# G803X.net
KiCad netlist of a schematic drawn in EAGLE
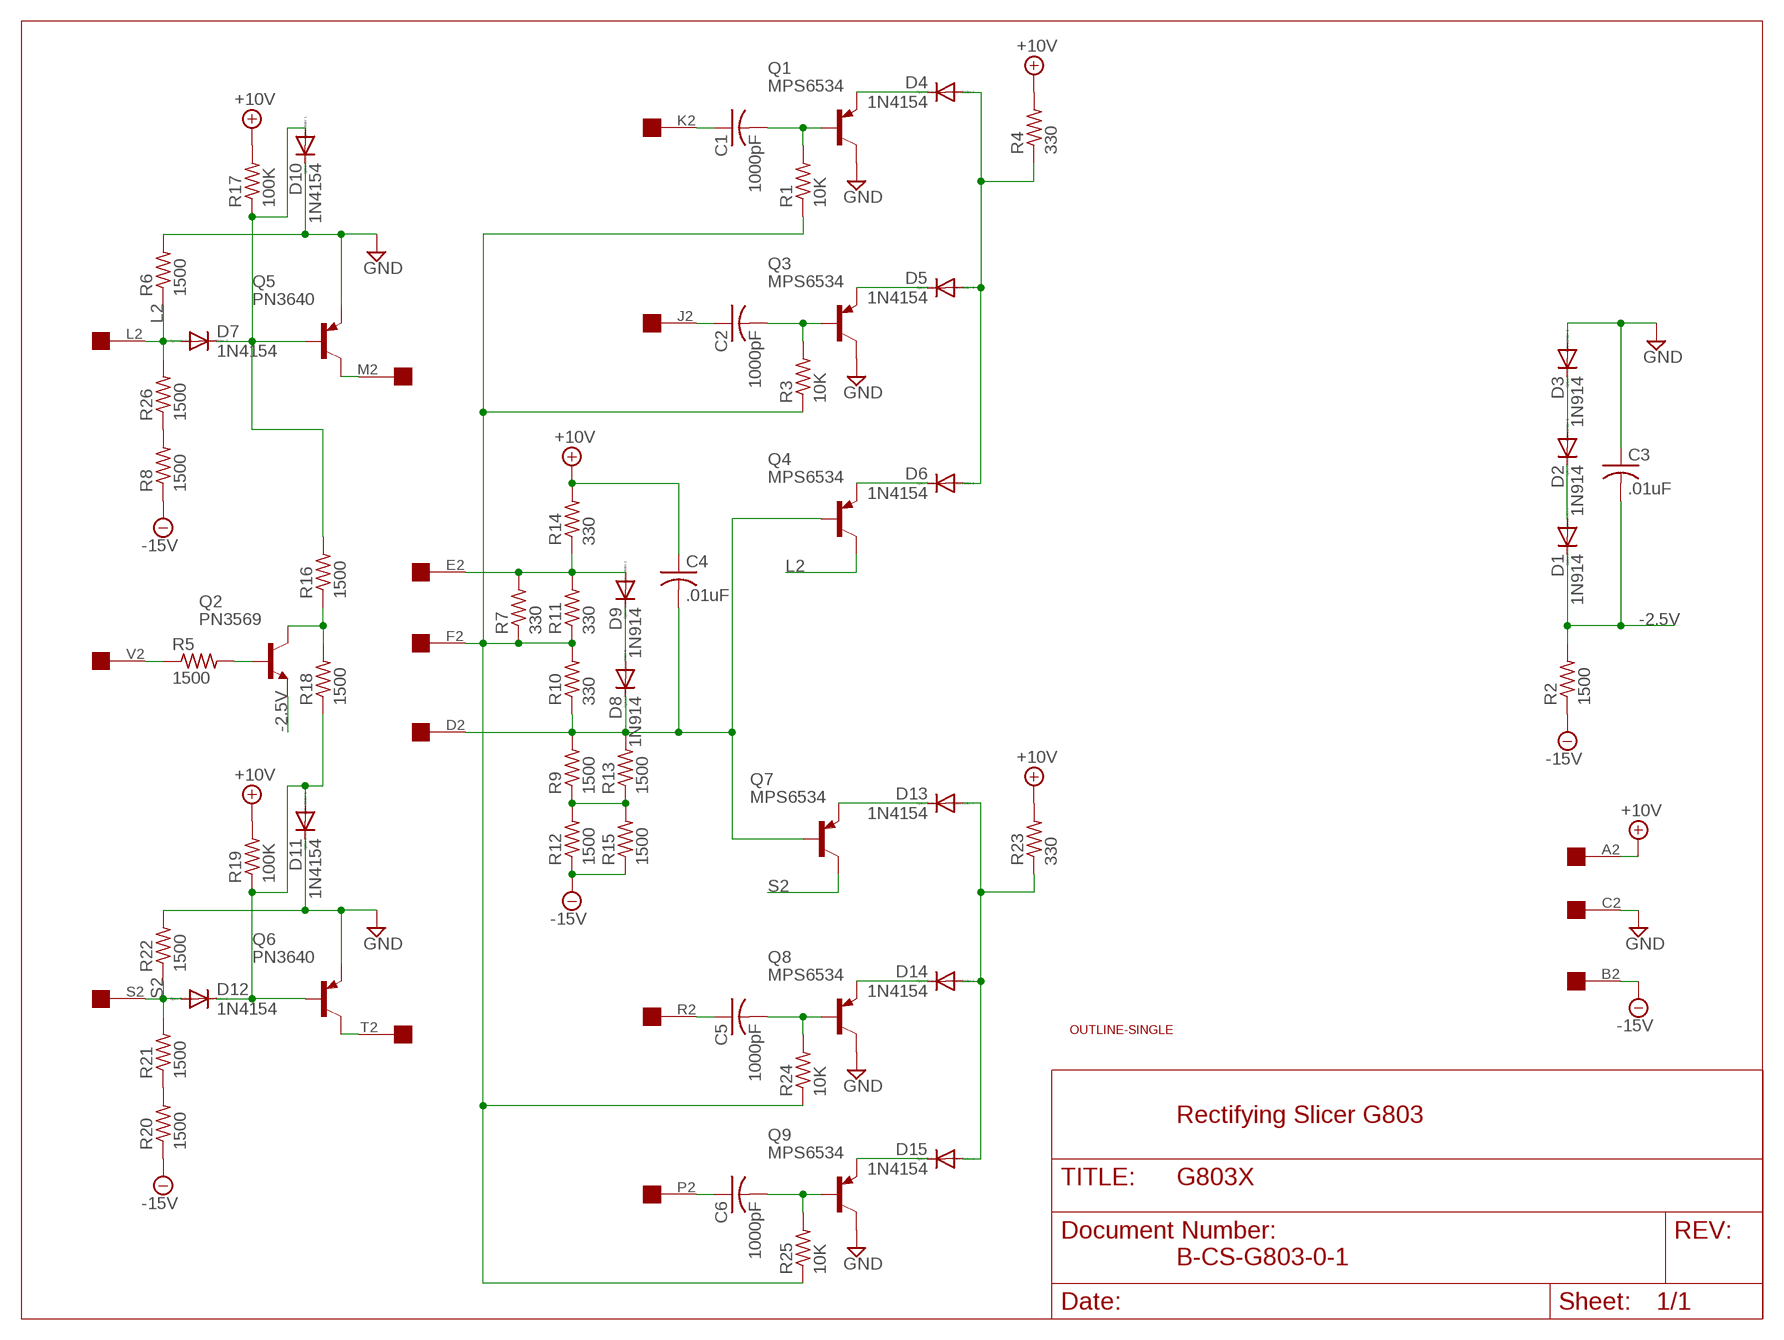
[diagram p0: schematic, sheet 1]

(export (version "E")
  (design (tool "Eeschema 10.0.6"))
  (components
    (comp (ref "C1")
      (value "1000pF")
      (footprint "eagle-import:C075-032X103")
      (libsource (lib "eagle-import") (part "C-US075-032X103"))
    )
    (comp (ref "C2")
      (value "1000pF")
      (footprint "eagle-import:C075-032X103")
      (libsource (lib "eagle-import") (part "C-US075-032X103"))
    )
    (comp (ref "C3")
      (value ".01uF")
      (footprint "eagle-import:C050-025X075")
      (libsource (lib "eagle-import") (part "C-US050-025X075"))
    )
    (comp (ref "C4")
      (value ".01uF")
      (footprint "eagle-import:C075-032X103")
      (libsource (lib "eagle-import") (part "C-US075-032X103"))
    )
    (comp (ref "C5")
      (value "1000pF")
      (footprint "eagle-import:C075-032X103")
      (libsource (lib "eagle-import") (part "C-US075-032X103"))
    )
    (comp (ref "C6")
      (value "1000pF")
      (footprint "eagle-import:C075-032X103")
      (libsource (lib "eagle-import") (part "C-US075-032X103"))
    )
    (comp (ref "D1")
      (value "1N914")
      (footprint "eagle-import:DO35-10")
      (libsource (lib "eagle-import") (part "1N4148DO35-10"))
    )
    (comp (ref "D2")
      (value "1N914")
      (footprint "eagle-import:DO35-10")
      (libsource (lib "eagle-import") (part "1N4148DO35-10"))
    )
    (comp (ref "D3")
      (value "1N914")
      (footprint "eagle-import:DO35-10")
      (libsource (lib "eagle-import") (part "1N4148DO35-10"))
    )
    (comp (ref "D4")
      (value "1N4154")
      (footprint "eagle-import:DO35-10")
      (libsource (lib "eagle-import") (part "1N4148DO35-10"))
    )
    (comp (ref "D5")
      (value "1N4154")
      (footprint "eagle-import:DO35-10")
      (libsource (lib "eagle-import") (part "1N4148DO35-10"))
    )
    (comp (ref "D6")
      (value "1N4154")
      (footprint "eagle-import:DO35-10")
      (libsource (lib "eagle-import") (part "1N4148DO35-10"))
    )
    (comp (ref "D7")
      (value "1N4154")
      (footprint "eagle-import:DO35-10")
      (libsource (lib "eagle-import") (part "1N4148DO35-10"))
    )
    (comp (ref "D8")
      (value "1N914")
      (footprint "eagle-import:DO35-10")
      (libsource (lib "eagle-import") (part "1N4148DO35-10"))
    )
    (comp (ref "D9")
      (value "1N914")
      (footprint "eagle-import:DO35-10")
      (libsource (lib "eagle-import") (part "1N4148DO35-10"))
    )
    (comp (ref "D10")
      (value "1N4154")
      (footprint "eagle-import:DO35-10")
      (libsource (lib "eagle-import") (part "1N4148DO35-10"))
    )
    (comp (ref "D11")
      (value "1N4154")
      (footprint "eagle-import:DO35-10")
      (libsource (lib "eagle-import") (part "1N4148DO35-10"))
    )
    (comp (ref "D12")
      (value "1N4154")
      (footprint "eagle-import:DO35-10")
      (libsource (lib "eagle-import") (part "1N4148DO35-10"))
    )
    (comp (ref "D13")
      (value "1N4154")
      (footprint "eagle-import:DO35-10")
      (libsource (lib "eagle-import") (part "1N4148DO35-10"))
    )
    (comp (ref "D14")
      (value "1N4154")
      (footprint "eagle-import:DO35-10")
      (libsource (lib "eagle-import") (part "1N4148DO35-10"))
    )
    (comp (ref "D15")
      (value "1N4154")
      (footprint "eagle-import:DO35-10")
      (libsource (lib "eagle-import") (part "1N4148DO35-10"))
    )
    (comp (ref "Q1")
      (value "MPS6534")
      (footprint "eagle-import:TO39")
      (libsource (lib "eagle-import") (part "2N2904"))
    )
    (comp (ref "Q2")
      (value "PN3569")
      (footprint "eagle-import:TO5")
      (libsource (lib "eagle-import") (part "2N2102"))
    )
    (comp (ref "Q3")
      (value "MPS6534")
      (footprint "eagle-import:TO39")
      (libsource (lib "eagle-import") (part "2N2904"))
    )
    (comp (ref "Q4")
      (value "MPS6534")
      (footprint "eagle-import:TO39")
      (libsource (lib "eagle-import") (part "2N2904"))
    )
    (comp (ref "Q5")
      (value "PN3640")
      (footprint "eagle-import:TO39")
      (libsource (lib "eagle-import") (part "2N2904"))
    )
    (comp (ref "Q6")
      (value "PN3640")
      (footprint "eagle-import:TO39")
      (libsource (lib "eagle-import") (part "2N2904"))
    )
    (comp (ref "Q7")
      (value "MPS6534")
      (footprint "eagle-import:TO39")
      (libsource (lib "eagle-import") (part "2N2904"))
    )
    (comp (ref "Q8")
      (value "MPS6534")
      (footprint "eagle-import:TO39")
      (libsource (lib "eagle-import") (part "2N2904"))
    )
    (comp (ref "Q9")
      (value "MPS6534")
      (footprint "eagle-import:TO39")
      (libsource (lib "eagle-import") (part "2N2904"))
    )
    (comp (ref "R1")
      (value "10K")
      (footprint "eagle-import:0207_10")
      (libsource (lib "eagle-import") (part "R-US_0207/10"))
    )
    (comp (ref "R2")
      (value "1500")
      (footprint "eagle-import:0207_10")
      (libsource (lib "eagle-import") (part "R-US_0207/10"))
    )
    (comp (ref "R3")
      (value "10K")
      (footprint "eagle-import:0207_10")
      (libsource (lib "eagle-import") (part "R-US_0207/10"))
    )
    (comp (ref "R4")
      (value "330")
      (footprint "eagle-import:0207_10")
      (libsource (lib "eagle-import") (part "R-US_0207/10"))
    )
    (comp (ref "R5")
      (value "1500")
      (footprint "eagle-import:0207_10")
      (libsource (lib "eagle-import") (part "R-US_0207/10"))
    )
    (comp (ref "R6")
      (value "1500")
      (footprint "eagle-import:0207_10")
      (libsource (lib "eagle-import") (part "R-US_0207/10"))
    )
    (comp (ref "R7")
      (value "330")
      (footprint "eagle-import:0207_10")
      (libsource (lib "eagle-import") (part "R-US_0207/10"))
    )
    (comp (ref "R8")
      (value "1500")
      (footprint "eagle-import:0207_10")
      (libsource (lib "eagle-import") (part "R-US_0207/10"))
    )
    (comp (ref "R9")
      (value "1500")
      (footprint "eagle-import:0207_10")
      (libsource (lib "eagle-import") (part "R-US_0207/10"))
    )
    (comp (ref "R10")
      (value "330")
      (footprint "eagle-import:0207_10")
      (libsource (lib "eagle-import") (part "R-US_0207/10"))
    )
    (comp (ref "R11")
      (value "330")
      (footprint "eagle-import:0207_10")
      (libsource (lib "eagle-import") (part "R-US_0207/10"))
    )
    (comp (ref "R12")
      (value "1500")
      (footprint "eagle-import:0207_10")
      (libsource (lib "eagle-import") (part "R-US_0207/10"))
    )
    (comp (ref "R13")
      (value "1500")
      (footprint "eagle-import:0207_10")
      (libsource (lib "eagle-import") (part "R-US_0207/10"))
    )
    (comp (ref "R14")
      (value "330")
      (footprint "eagle-import:0207_10")
      (libsource (lib "eagle-import") (part "R-US_0207/10"))
    )
    (comp (ref "R15")
      (value "1500")
      (footprint "eagle-import:0207_10")
      (libsource (lib "eagle-import") (part "R-US_0207/10"))
    )
    (comp (ref "R16")
      (value "1500")
      (footprint "eagle-import:0207_10")
      (libsource (lib "eagle-import") (part "R-US_0207/10"))
    )
    (comp (ref "R17")
      (value "100K")
      (footprint "eagle-import:0207_10")
      (libsource (lib "eagle-import") (part "R-US_0207/10"))
    )
    (comp (ref "R18")
      (value "1500")
      (footprint "eagle-import:0207_10")
      (libsource (lib "eagle-import") (part "R-US_0207/10"))
    )
    (comp (ref "R19")
      (value "100K")
      (footprint "eagle-import:0207_10")
      (libsource (lib "eagle-import") (part "R-US_0207/10"))
    )
    (comp (ref "R20")
      (value "1500")
      (footprint "eagle-import:0207_10")
      (libsource (lib "eagle-import") (part "R-US_0207/10"))
    )
    (comp (ref "R21")
      (value "1500")
      (footprint "eagle-import:0207_10")
      (libsource (lib "eagle-import") (part "R-US_0207/10"))
    )
    (comp (ref "R22")
      (value "1500")
      (footprint "eagle-import:0207_10")
      (libsource (lib "eagle-import") (part "R-US_0207/10"))
    )
    (comp (ref "R23")
      (value "330")
      (footprint "eagle-import:0207_10")
      (libsource (lib "eagle-import") (part "R-US_0207/10"))
    )
    (comp (ref "R24")
      (value "10K")
      (footprint "eagle-import:0207_10")
      (libsource (lib "eagle-import") (part "R-US_0207/10"))
    )
    (comp (ref "R25")
      (value "10K")
      (footprint "eagle-import:0207_10")
      (libsource (lib "eagle-import") (part "R-US_0207/10"))
    )
    (comp (ref "R26")
      (value "1500")
      (footprint "eagle-import:0207_10")
      (libsource (lib "eagle-import") (part "R-US_0207/10"))
    )
    (comp (ref "U$1")
      (value "OUTLINE-SINGLE")
      (footprint "eagle-import:SINGLE")
      (libsource (lib "eagle-import") (part "OUTLINE-SINGLE"))
    )
    (comp (ref "U$2")
      (value "EDGE-1")
      (footprint "eagle-import:EDGE-CON1")
      (libsource (lib "eagle-import") (part "EDGE-1"))
    )
  )
  (nets
    (net (code "1") (name "+10V") (class "Default")
      (node (ref "C4") (pin "1") (pinfunction "1_1") (pintype "passive"))
      (node (ref "R14") (pin "2") (pinfunction "2_2") (pintype "passive"))
      (node (ref "R17") (pin "2") (pinfunction "2_2") (pintype "passive"))
      (node (ref "R19") (pin "2") (pinfunction "2_2") (pintype "passive"))
      (node (ref "R23") (pin "2") (pinfunction "2_2") (pintype "passive"))
      (node (ref "R4") (pin "2") (pinfunction "2_2") (pintype "passive"))
      (node (ref "U$2") (pin "A2") (pinfunction "1_A2") (pintype "bidirectional"))
    )
    (net (code "2") (name "-15V") (class "Default")
      (node (ref "R12") (pin "1") (pinfunction "1_1") (pintype "passive"))
      (node (ref "R15") (pin "1") (pinfunction "1_1") (pintype "passive"))
      (node (ref "R2") (pin "1") (pinfunction "1_1") (pintype "passive"))
      (node (ref "R20") (pin "1") (pinfunction "1_1") (pintype "passive"))
      (node (ref "R8") (pin "1") (pinfunction "1_1") (pintype "passive"))
      (node (ref "U$2") (pin "B2") (pinfunction "1_B2") (pintype "bidirectional"))
    )
    (net (code "3") (name "/-2.5V") (class "Default")
      (node (ref "C3") (pin "2") (pinfunction "2_2") (pintype "passive"))
      (node (ref "D1") (pin "C") (pinfunction "C_C") (pintype "passive"))
      (node (ref "Q2") (pin "1") (pinfunction "E_1") (pintype "passive"))
      (node (ref "R2") (pin "2") (pinfunction "2_2") (pintype "passive"))
    )
    (net (code "4") (name "/L2") (class "Default")
      (node (ref "D7") (pin "A") (pinfunction "A_A") (pintype "passive"))
      (node (ref "Q4") (pin "3") (pinfunction "C_3") (pintype "passive"))
      (node (ref "R26") (pin "2") (pinfunction "2_2") (pintype "passive"))
      (node (ref "R6") (pin "1") (pinfunction "1_1") (pintype "passive"))
      (node (ref "U$2") (pin "L2") (pinfunction "1_L2") (pintype "bidirectional"))
    )
    (net (code "5") (name "/S2") (class "Default")
      (node (ref "D12") (pin "A") (pinfunction "A_A") (pintype "passive"))
      (node (ref "Q7") (pin "3") (pinfunction "C_3") (pintype "passive"))
      (node (ref "R21") (pin "2") (pinfunction "2_2") (pintype "passive"))
      (node (ref "R22") (pin "1") (pinfunction "1_1") (pintype "passive"))
      (node (ref "U$2") (pin "S2") (pinfunction "1_S2") (pintype "bidirectional"))
    )
    (net (code "6") (name "GND") (class "Default")
      (node (ref "C3") (pin "1") (pinfunction "1_1") (pintype "passive"))
      (node (ref "D10") (pin "C") (pinfunction "C_C") (pintype "passive"))
      (node (ref "D11") (pin "C") (pinfunction "C_C") (pintype "passive"))
      (node (ref "D3") (pin "A") (pinfunction "A_A") (pintype "passive"))
      (node (ref "Q1") (pin "3") (pinfunction "C_3") (pintype "passive"))
      (node (ref "Q3") (pin "3") (pinfunction "C_3") (pintype "passive"))
      (node (ref "Q5") (pin "1") (pinfunction "E_1") (pintype "passive"))
      (node (ref "Q6") (pin "1") (pinfunction "E_1") (pintype "passive"))
      (node (ref "Q8") (pin "3") (pinfunction "C_3") (pintype "passive"))
      (node (ref "Q9") (pin "3") (pinfunction "C_3") (pintype "passive"))
      (node (ref "R22") (pin "2") (pinfunction "2_2") (pintype "passive"))
      (node (ref "R6") (pin "2") (pinfunction "2_2") (pintype "passive"))
      (node (ref "U$2") (pin "C2") (pinfunction "1_C2") (pintype "bidirectional"))
    )
    (net (code "7") (name "Net-(D1-PadA)") (class "Default")
      (node (ref "D1") (pin "A") (pinfunction "A_A") (pintype "passive"))
      (node (ref "D2") (pin "C") (pinfunction "C_C") (pintype "passive"))
    )
    (net (code "8") (name "Net-(D2-PadA)") (class "Default")
      (node (ref "D2") (pin "A") (pinfunction "A_A") (pintype "passive"))
      (node (ref "D3") (pin "C") (pinfunction "C_C") (pintype "passive"))
    )
    (net (code "9") (name "Net-(D4-PadA)") (class "Default")
      (node (ref "D4") (pin "A") (pinfunction "A_A") (pintype "passive"))
      (node (ref "D5") (pin "A") (pinfunction "A_A") (pintype "passive"))
      (node (ref "D6") (pin "A") (pinfunction "A_A") (pintype "passive"))
      (node (ref "R4") (pin "1") (pinfunction "1_1") (pintype "passive"))
    )
    (net (code "10") (name "Net-(D8-PadA)") (class "Default")
      (node (ref "D8") (pin "A") (pinfunction "A_A") (pintype "passive"))
      (node (ref "D9") (pin "C") (pinfunction "C_C") (pintype "passive"))
    )
    (net (code "11") (name "Net-(D13-PadA)") (class "Default")
      (node (ref "D13") (pin "A") (pinfunction "A_A") (pintype "passive"))
      (node (ref "D14") (pin "A") (pinfunction "A_A") (pintype "passive"))
      (node (ref "D15") (pin "A") (pinfunction "A_A") (pintype "passive"))
      (node (ref "R23") (pin "1") (pinfunction "1_1") (pintype "passive"))
    )
    (net (code "12") (name "Net-(Q1-B)") (class "Default")
      (node (ref "C1") (pin "2") (pinfunction "2_2") (pintype "passive"))
      (node (ref "Q1") (pin "2") (pinfunction "B_2") (pintype "passive"))
      (node (ref "R1") (pin "2") (pinfunction "2_2") (pintype "passive"))
    )
    (net (code "13") (name "Net-(Q1-E)") (class "Default")
      (node (ref "D4") (pin "C") (pinfunction "C_C") (pintype "passive"))
      (node (ref "Q1") (pin "1") (pinfunction "E_1") (pintype "passive"))
    )
    (net (code "14") (name "Net-(Q2-B)") (class "Default")
      (node (ref "Q2") (pin "2") (pinfunction "B_2") (pintype "passive"))
      (node (ref "R5") (pin "2") (pinfunction "2_2") (pintype "passive"))
    )
    (net (code "15") (name "Net-(Q2-C)") (class "Default")
      (node (ref "Q2") (pin "3") (pinfunction "C_3") (pintype "passive"))
      (node (ref "R16") (pin "1") (pinfunction "1_1") (pintype "passive"))
      (node (ref "R18") (pin "2") (pinfunction "2_2") (pintype "passive"))
    )
    (net (code "16") (name "Net-(Q3-B)") (class "Default")
      (node (ref "C2") (pin "2") (pinfunction "2_2") (pintype "passive"))
      (node (ref "Q3") (pin "2") (pinfunction "B_2") (pintype "passive"))
      (node (ref "R3") (pin "2") (pinfunction "2_2") (pintype "passive"))
    )
    (net (code "17") (name "Net-(Q3-E)") (class "Default")
      (node (ref "D5") (pin "C") (pinfunction "C_C") (pintype "passive"))
      (node (ref "Q3") (pin "1") (pinfunction "E_1") (pintype "passive"))
    )
    (net (code "18") (name "Net-(Q4-B)") (class "Default")
      (node (ref "C4") (pin "2") (pinfunction "2_2") (pintype "passive"))
      (node (ref "D8") (pin "C") (pinfunction "C_C") (pintype "passive"))
      (node (ref "Q4") (pin "2") (pinfunction "B_2") (pintype "passive"))
      (node (ref "Q7") (pin "2") (pinfunction "B_2") (pintype "passive"))
      (node (ref "R10") (pin "1") (pinfunction "1_1") (pintype "passive"))
      (node (ref "R13") (pin "2") (pinfunction "2_2") (pintype "passive"))
      (node (ref "R9") (pin "2") (pinfunction "2_2") (pintype "passive"))
      (node (ref "U$2") (pin "D2") (pinfunction "1_D2") (pintype "bidirectional"))
    )
    (net (code "19") (name "Net-(Q4-E)") (class "Default")
      (node (ref "D6") (pin "C") (pinfunction "C_C") (pintype "passive"))
      (node (ref "Q4") (pin "1") (pinfunction "E_1") (pintype "passive"))
    )
    (net (code "20") (name "Net-(Q5-B)") (class "Default")
      (node (ref "D10") (pin "A") (pinfunction "A_A") (pintype "passive"))
      (node (ref "D7") (pin "C") (pinfunction "C_C") (pintype "passive"))
      (node (ref "Q5") (pin "2") (pinfunction "B_2") (pintype "passive"))
      (node (ref "R16") (pin "2") (pinfunction "2_2") (pintype "passive"))
      (node (ref "R17") (pin "1") (pinfunction "1_1") (pintype "passive"))
    )
    (net (code "21") (name "Net-(Q5-C)") (class "Default")
      (node (ref "Q5") (pin "3") (pinfunction "C_3") (pintype "passive"))
      (node (ref "U$2") (pin "M2") (pinfunction "1_M2") (pintype "bidirectional"))
    )
    (net (code "22") (name "Net-(Q6-B)") (class "Default")
      (node (ref "D11") (pin "A") (pinfunction "A_A") (pintype "passive"))
      (node (ref "D12") (pin "C") (pinfunction "C_C") (pintype "passive"))
      (node (ref "Q6") (pin "2") (pinfunction "B_2") (pintype "passive"))
      (node (ref "R18") (pin "1") (pinfunction "1_1") (pintype "passive"))
      (node (ref "R19") (pin "1") (pinfunction "1_1") (pintype "passive"))
    )
    (net (code "23") (name "Net-(Q6-C)") (class "Default")
      (node (ref "Q6") (pin "3") (pinfunction "C_3") (pintype "passive"))
      (node (ref "U$2") (pin "T2") (pinfunction "1_T2") (pintype "bidirectional"))
    )
    (net (code "24") (name "Net-(Q7-E)") (class "Default")
      (node (ref "D13") (pin "C") (pinfunction "C_C") (pintype "passive"))
      (node (ref "Q7") (pin "1") (pinfunction "E_1") (pintype "passive"))
    )
    (net (code "25") (name "Net-(Q8-B)") (class "Default")
      (node (ref "C5") (pin "2") (pinfunction "2_2") (pintype "passive"))
      (node (ref "Q8") (pin "2") (pinfunction "B_2") (pintype "passive"))
      (node (ref "R24") (pin "2") (pinfunction "2_2") (pintype "passive"))
    )
    (net (code "26") (name "Net-(Q8-E)") (class "Default")
      (node (ref "D14") (pin "C") (pinfunction "C_C") (pintype "passive"))
      (node (ref "Q8") (pin "1") (pinfunction "E_1") (pintype "passive"))
    )
    (net (code "27") (name "Net-(Q9-B)") (class "Default")
      (node (ref "C6") (pin "2") (pinfunction "2_2") (pintype "passive"))
      (node (ref "Q9") (pin "2") (pinfunction "B_2") (pintype "passive"))
      (node (ref "R25") (pin "2") (pinfunction "2_2") (pintype "passive"))
    )
    (net (code "28") (name "Net-(Q9-E)") (class "Default")
      (node (ref "D15") (pin "C") (pinfunction "C_C") (pintype "passive"))
      (node (ref "Q9") (pin "1") (pinfunction "E_1") (pintype "passive"))
    )
    (net (code "29") (name "Net-(R12-Pad2)") (class "Default")
      (node (ref "R12") (pin "2") (pinfunction "2_2") (pintype "passive"))
      (node (ref "R13") (pin "1") (pinfunction "1_1") (pintype "passive"))
      (node (ref "R15") (pin "2") (pinfunction "2_2") (pintype "passive"))
      (node (ref "R9") (pin "1") (pinfunction "1_1") (pintype "passive"))
    )
    (net (code "30") (name "Net-(R20-Pad2)") (class "Default")
      (node (ref "R20") (pin "2") (pinfunction "2_2") (pintype "passive"))
      (node (ref "R21") (pin "1") (pinfunction "1_1") (pintype "passive"))
    )
    (net (code "31") (name "Net-(R26-Pad1)") (class "Default")
      (node (ref "R26") (pin "1") (pinfunction "1_1") (pintype "passive"))
      (node (ref "R8") (pin "2") (pinfunction "2_2") (pintype "passive"))
    )
    (net (code "32") (name "Net-(U$2E-1)") (class "Default")
      (node (ref "D9") (pin "A") (pinfunction "A_A") (pintype "passive"))
      (node (ref "R11") (pin "2") (pinfunction "2_2") (pintype "passive"))
      (node (ref "R14") (pin "1") (pinfunction "1_1") (pintype "passive"))
      (node (ref "R7") (pin "2") (pinfunction "2_2") (pintype "passive"))
      (node (ref "U$2") (pin "E2") (pinfunction "1_E2") (pintype "bidirectional"))
    )
    (net (code "33") (name "Net-(U$2F-1)") (class "Default")
      (node (ref "R1") (pin "1") (pinfunction "1_1") (pintype "passive"))
      (node (ref "R10") (pin "2") (pinfunction "2_2") (pintype "passive"))
      (node (ref "R11") (pin "1") (pinfunction "1_1") (pintype "passive"))
      (node (ref "R24") (pin "1") (pinfunction "1_1") (pintype "passive"))
      (node (ref "R25") (pin "1") (pinfunction "1_1") (pintype "passive"))
      (node (ref "R3") (pin "1") (pinfunction "1_1") (pintype "passive"))
      (node (ref "R7") (pin "1") (pinfunction "1_1") (pintype "passive"))
      (node (ref "U$2") (pin "F2") (pinfunction "1_F2") (pintype "bidirectional"))
    )
    (net (code "34") (name "Net-(U$2H-1)") (class "Default")
      (node (ref "C2") (pin "1") (pinfunction "1_1") (pintype "passive"))
      (node (ref "U$2") (pin "J2") (pinfunction "1_J2") (pintype "bidirectional"))
    )
    (net (code "35") (name "Net-(U$2I-1)") (class "Default")
      (node (ref "C1") (pin "1") (pinfunction "1_1") (pintype "passive"))
      (node (ref "U$2") (pin "K2") (pinfunction "1_K2") (pintype "bidirectional"))
    )
    (net (code "36") (name "Net-(U$2M-1)") (class "Default")
      (node (ref "C6") (pin "1") (pinfunction "1_1") (pintype "passive"))
      (node (ref "U$2") (pin "P2") (pinfunction "1_P2") (pintype "bidirectional"))
    )
    (net (code "37") (name "Net-(U$2N-1)") (class "Default")
      (node (ref "C5") (pin "1") (pinfunction "1_1") (pintype "passive"))
      (node (ref "U$2") (pin "R2") (pinfunction "1_R2") (pintype "bidirectional"))
    )
    (net (code "38") (name "Net-(U$2R-1)") (class "Default")
      (node (ref "R5") (pin "1") (pinfunction "1_1") (pintype "passive"))
      (node (ref "U$2") (pin "V2") (pinfunction "1_V2") (pintype "bidirectional"))
    )
  )
)
